# v0_6_1.net
KiCad netlist of a schematic drawn in EAGLE
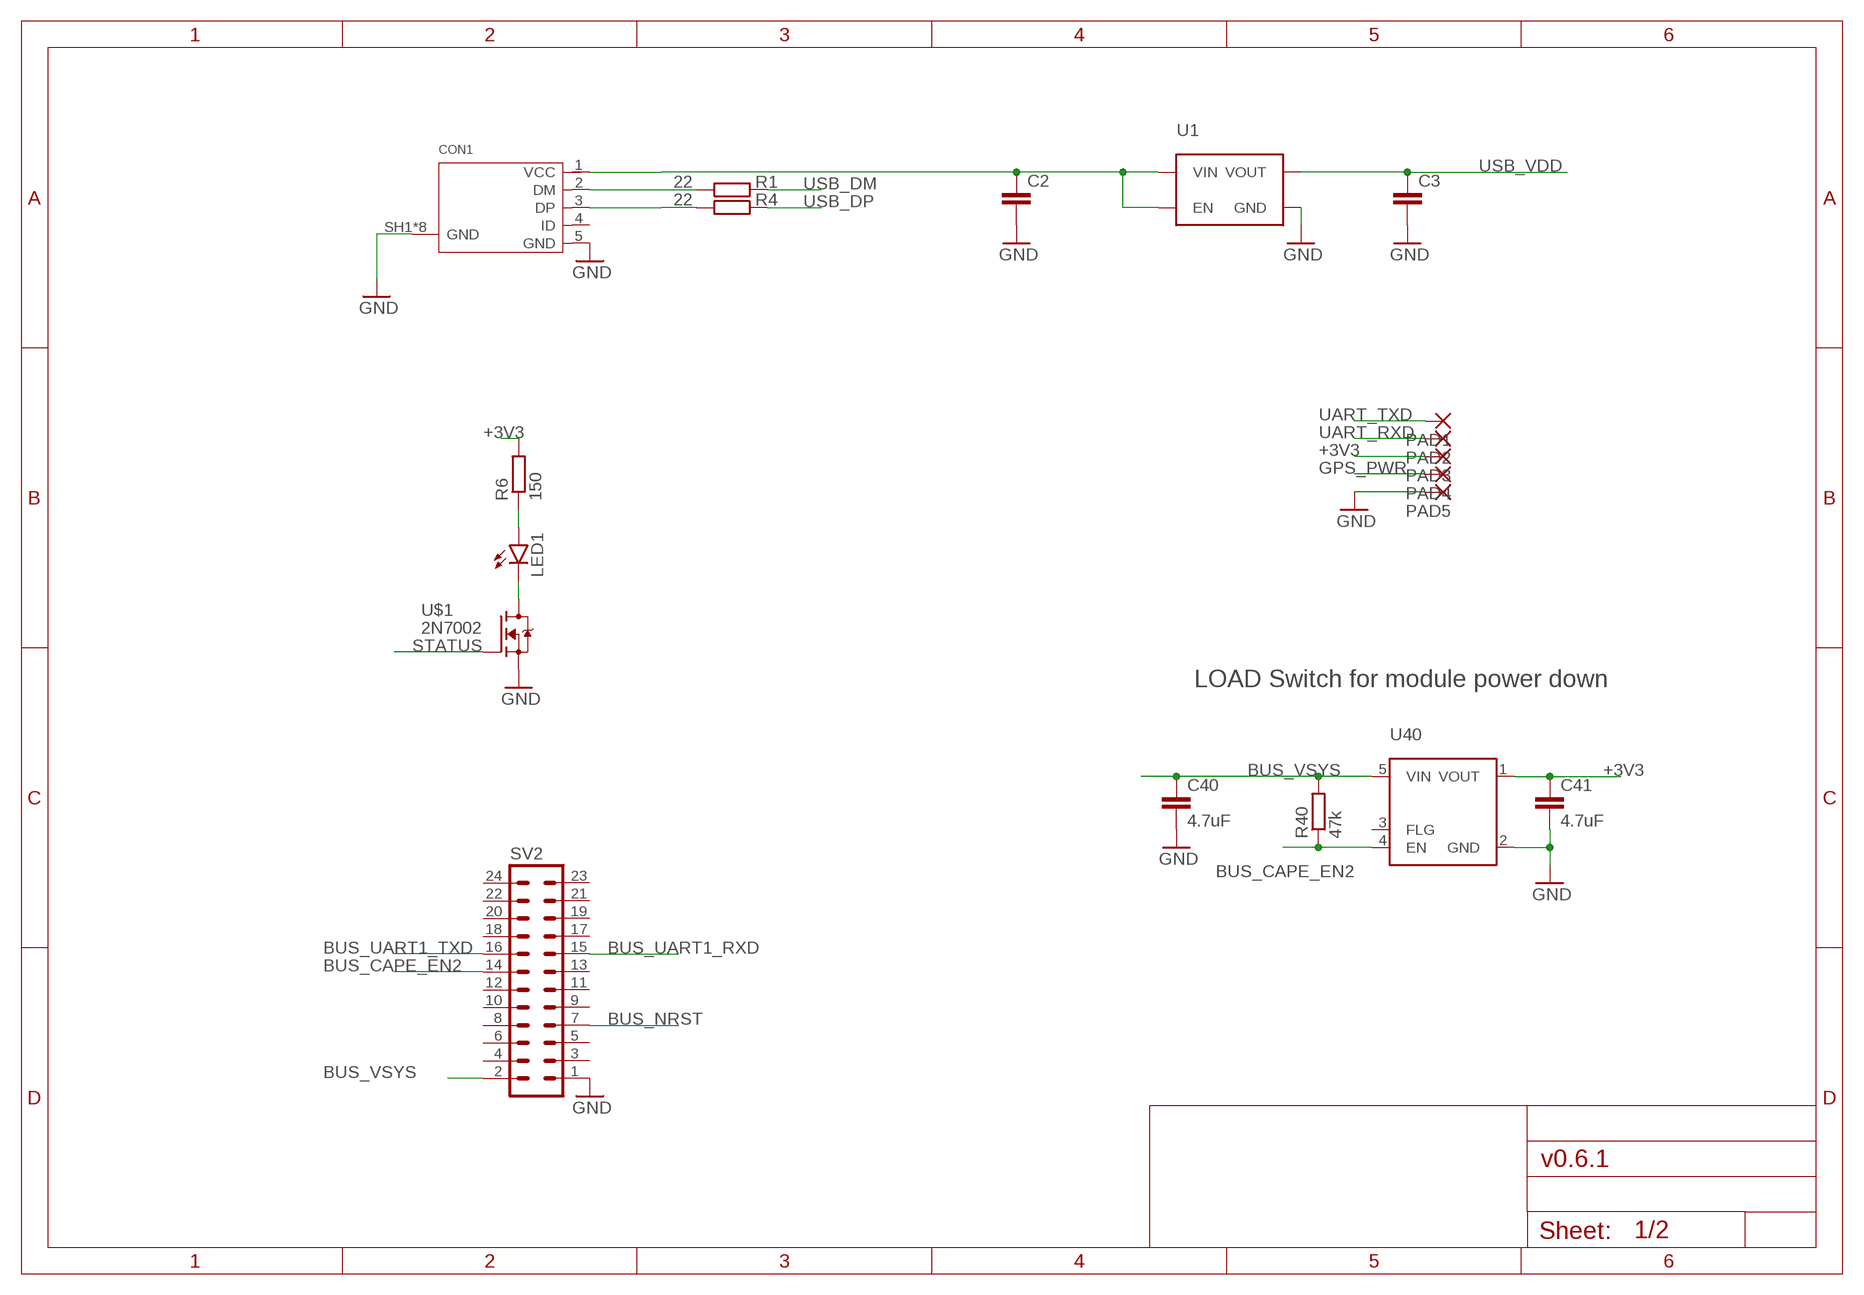
[diagram p0: schematic, sheet 1]
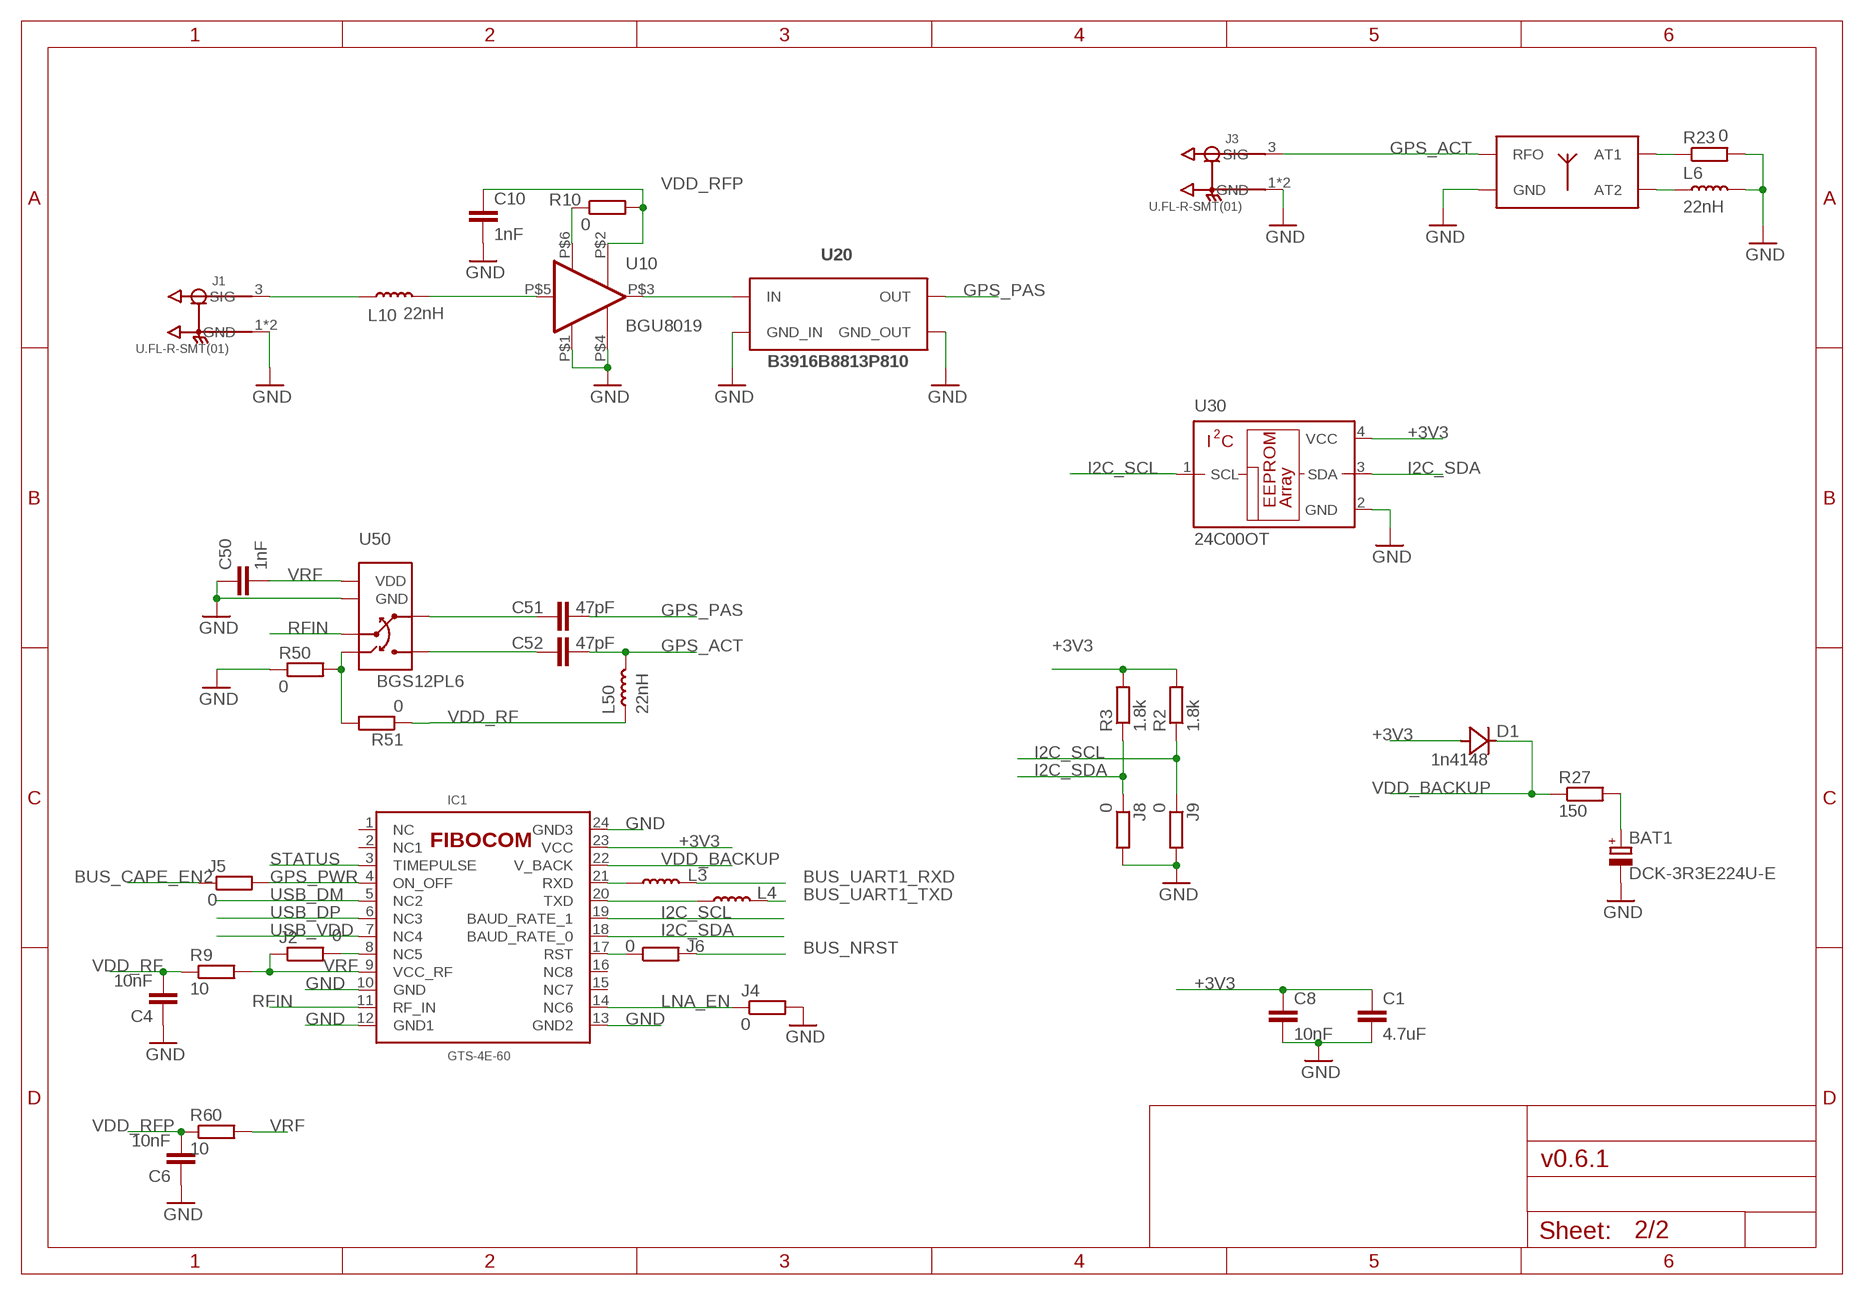
[diagram p1: schematic, sheet 2]

(export (version "E")
  (design (tool "Eeschema 10.0.6"))
  (components
    (comp (ref "ANT1")
      (value "M20047")
      (footprint "eagle-import:PCBCOMPONENT_1")
      (libsource (lib "eagle-import") (part "M20047"))
    )
    (comp (ref "BAT1")
      (value "DCK-3R3E224U-E")
      (footprint "eagle-import:621")
      (libsource (lib "eagle-import") (part "DCK-3R3E224U-E"))
    )
    (comp (ref "C1")
      (value "4.7uF")
      (footprint "eagle-import:C0603")
      (libsource (lib "eagle-import") (part "C-EUC0603"))
    )
    (comp (ref "C4")
      (value "10nF")
      (footprint "eagle-import:C0402K")
      (libsource (lib "eagle-import") (part "CAP-0402"))
    )
    (comp (ref "C6")
      (value "10nF")
      (footprint "eagle-import:C0402K")
      (libsource (lib "eagle-import") (part "CAP-0402"))
    )
    (comp (ref "C8")
      (value "10nF")
      (footprint "eagle-import:C0402K")
      (libsource (lib "eagle-import") (part "CAP-0402"))
    )
    (comp (ref "C10")
      (value "1nF")
      (footprint "eagle-import:C0402K")
      (libsource (lib "eagle-import") (part "CAP-0402"))
    )
    (comp (ref "C50")
      (value "1nF")
      (footprint "eagle-import:C0402K")
      (libsource (lib "eagle-import") (part "CAP-0402"))
    )
    (comp (ref "C51")
      (value "47pF")
      (footprint "eagle-import:C0402K")
      (libsource (lib "eagle-import") (part "CAP-0402"))
    )
    (comp (ref "C52")
      (value "47pF")
      (footprint "eagle-import:C0402K")
      (libsource (lib "eagle-import") (part "CAP-0402"))
    )
    (comp (ref "D1")
      (value "1n4148")
      (footprint "eagle-import:SOD323")
      (libsource (lib "eagle-import") (part "1N4148WS"))
    )
    (comp (ref "IC1")
      (value "GTS-4E-60")
      (footprint "eagle-import:_GTS_4E_60")
      (libsource (lib "eagle-import") (part "GTS-4E-60"))
    )
    (comp (ref "J1")
      (value "U.FL-R-SMT(01)")
      (footprint "eagle-import:HRS_U.FL-R-SMT(01)")
      (fields (field (name "MF") "Hirose") (field (name "MP") "U.FL-R-SMT_01_"))
      (libsource (lib "eagle-import") (part "U.FL-R-SMT(01)"))
    )
    (comp (ref "J2")
      (value "0")
      (footprint "eagle-import:R0402")
      (libsource (lib "eagle-import") (part "R-EU_R0402"))
    )
    (comp (ref "J3")
      (value "U.FL-R-SMT(01)")
      (footprint "eagle-import:HRS_U.FL-R-SMT(01)")
      (fields (field (name "MF") "Hirose") (field (name "MP") "U.FL-R-SMT_01_"))
      (libsource (lib "eagle-import") (part "U.FL-R-SMT(01)"))
    )
    (comp (ref "J4")
      (value "0")
      (footprint "eagle-import:R0402")
      (libsource (lib "eagle-import") (part "R-EU_R0402"))
    )
    (comp (ref "J5")
      (value "0")
      (footprint "eagle-import:R0402")
      (libsource (lib "eagle-import") (part "R-EU_R0402"))
    )
    (comp (ref "J6")
      (value "0")
      (footprint "eagle-import:R0402")
      (libsource (lib "eagle-import") (part "R-EU_R0402"))
    )
    (comp (ref "J8")
      (value "0")
      (footprint "eagle-import:R0402")
      (libsource (lib "eagle-import") (part "R-EU_R0402"))
    )
    (comp (ref "J9")
      (value "0")
      (footprint "eagle-import:R0402")
      (libsource (lib "eagle-import") (part "R-EU_R0402"))
    )
    (comp (ref "L3")
      (value "blm15")
      (footprint "eagle-import:L0402")
      (libsource (lib "eagle-import") (part "IND-0402"))
    )
    (comp (ref "L4")
      (value "blm15")
      (footprint "eagle-import:L0402")
      (libsource (lib "eagle-import") (part "IND-0402"))
    )
    (comp (ref "L6")
      (value "22nH")
      (footprint "eagle-import:L0402")
      (libsource (lib "eagle-import") (part "IND-0402"))
    )
    (comp (ref "L10")
      (value "22nH")
      (footprint "eagle-import:L0402")
      (libsource (lib "eagle-import") (part "IND-0402"))
    )
    (comp (ref "L50")
      (value "22nH")
      (footprint "eagle-import:L0402")
      (libsource (lib "eagle-import") (part "IND-0402"))
    )
    (comp (ref "R2")
      (value "1.8k")
      (footprint "eagle-import:R0402")
      (libsource (lib "eagle-import") (part "R-EU_R0402"))
    )
    (comp (ref "R3")
      (value "1.8k")
      (footprint "eagle-import:R0402")
      (libsource (lib "eagle-import") (part "R-EU_R0402"))
    )
    (comp (ref "R9")
      (value "10")
      (footprint "eagle-import:R0402")
      (libsource (lib "eagle-import") (part "R-EU_R0402"))
    )
    (comp (ref "R10")
      (value "0")
      (footprint "eagle-import:R0402")
      (libsource (lib "eagle-import") (part "R-EU_R0402"))
    )
    (comp (ref "R23")
      (value "0")
      (footprint "eagle-import:R0402")
      (libsource (lib "eagle-import") (part "R-EU_R0402"))
    )
    (comp (ref "R27")
      (value "150")
      (footprint "eagle-import:R0402")
      (libsource (lib "eagle-import") (part "R-EU_R0402"))
    )
    (comp (ref "R50")
      (value "0")
      (footprint "eagle-import:R0402")
      (libsource (lib "eagle-import") (part "R-EU_R0402"))
    )
    (comp (ref "R51")
      (value "0")
      (footprint "eagle-import:R0402")
      (libsource (lib "eagle-import") (part "R-EU_R0402"))
    )
    (comp (ref "R60")
      (value "10")
      (footprint "eagle-import:R0402")
      (libsource (lib "eagle-import") (part "R-EU_R0402"))
    )
    (comp (ref "U10")
      (value "BGU8019")
      (footprint "eagle-import:XSON6")
      (libsource (lib "eagle-import") (part "BGU8019"))
    )
    (comp (ref "U20")
      (value "B3916B8813P810")
      (footprint "eagle-import:XSON5")
      (libsource (lib "eagle-import") (part "B3916B8813P810"))
    )
    (comp (ref "U30")
      (value "24C00OT")
      (footprint "eagle-import:SOT23-5L")
      (fields (field (name "MF") "MICROCHIP") (field (name "MPN") "24C00T-I/OT"))
      (libsource (lib "eagle-import") (part "2400OTC"))
    )
    (comp (ref "U50")
      (value "BGS12PL6")
      (footprint "eagle-import:TSLP-6-4")
      (libsource (lib "eagle-import") (part "BGS12PL6"))
    )
    (comp (ref "C2")
      (value "C-EUC0603")
      (footprint "eagle-import:C0603")
      (libsource (lib "eagle-import") (part "C-EUC0603"))
    )
    (comp (ref "C3")
      (value "C-EUC0603")
      (footprint "eagle-import:C0603")
      (libsource (lib "eagle-import") (part "C-EUC0603"))
    )
    (comp (ref "C40")
      (value "4.7uF")
      (footprint "eagle-import:C0603")
      (libsource (lib "eagle-import") (part "C-EUC0603"))
    )
    (comp (ref "C41")
      (value "4.7uF")
      (footprint "eagle-import:C0603")
      (libsource (lib "eagle-import") (part "C-EUC0603"))
    )
    (comp (ref "CON1")
      (value "10118194-0001LF")
      (footprint "eagle-import:10118194")
      (libsource (lib "eagle-import") (part "10118194-0001LF"))
    )
    (comp (ref "LED1")
      (value "LEDCHIP-LED0603")
      (footprint "eagle-import:CHIP-LED0603")
      (libsource (lib "eagle-import") (part "LEDCHIP-LED0603"))
    )
    (comp (ref "PAD1")
      (value "1,6/0,9")
      (footprint "eagle-import:1,6_0,9")
      (libsource (lib "eagle-import") (part "1,6/0,9"))
    )
    (comp (ref "PAD2")
      (value "1,6/0,9")
      (footprint "eagle-import:1,6_0,9")
      (libsource (lib "eagle-import") (part "1,6/0,9"))
    )
    (comp (ref "PAD3")
      (value "1,6/0,9")
      (footprint "eagle-import:1,6_0,9")
      (libsource (lib "eagle-import") (part "1,6/0,9"))
    )
    (comp (ref "PAD4")
      (value "1,6/0,9")
      (footprint "eagle-import:1,6_0,9")
      (libsource (lib "eagle-import") (part "1,6/0,9"))
    )
    (comp (ref "PAD5")
      (value "1,6/0,9")
      (footprint "eagle-import:1,6_0,9")
      (libsource (lib "eagle-import") (part "1,6/0,9"))
    )
    (comp (ref "R1")
      (value "22")
      (footprint "eagle-import:R0402")
      (libsource (lib "eagle-import") (part "R-EU_R0402"))
    )
    (comp (ref "R4")
      (value "22")
      (footprint "eagle-import:R0402")
      (libsource (lib "eagle-import") (part "R-EU_R0402"))
    )
    (comp (ref "R6")
      (value "150")
      (footprint "eagle-import:R0402")
      (libsource (lib "eagle-import") (part "R-EU_R0402"))
    )
    (comp (ref "R40")
      (value "47k")
      (footprint "eagle-import:R0402")
      (libsource (lib "eagle-import") (part "R-EU_R0402"))
    )
    (comp (ref "SV2")
      (value "MA12-2")
      (footprint "eagle-import:MA12-2")
      (libsource (lib "eagle-import") (part "MA12-2"))
    )
    (comp (ref "U$1")
      (value "2N7002")
      (footprint "eagle-import:SOT95P240X110-3")
      (libsource (lib "eagle-import") (part "2N7002"))
    )
    (comp (ref "U1")
      (value "MIC94310")
      (footprint "eagle-import:SOT95P280X110-5")
      (libsource (lib "eagle-import") (part "MIC94310"))
    )
    (comp (ref "U40")
      (value "AP22802b")
      (footprint "eagle-import:SOT25")
      (libsource (lib "eagle-import") (part "AP22802"))
    )
  )
  (nets
    (net (code "1") (name "+3V3") (class "Default")
      (node (ref "C1") (pin "1") (pinfunction "1_1") (pintype "passive"))
      (node (ref "C41") (pin "1") (pinfunction "1_1") (pintype "passive"))
      (node (ref "C8") (pin "1") (pinfunction "1_1") (pintype "passive"))
      (node (ref "D1") (pin "A") (pinfunction "A_A") (pintype "passive"))
      (node (ref "IC1") (pin "23") (pinfunction "VCC_23") (pintype "bidirectional"))
      (node (ref "PAD3") (pin "1") (pinfunction "P_1") (pintype "passive"))
      (node (ref "R2") (pin "2") (pinfunction "2_2") (pintype "passive"))
      (node (ref "R3") (pin "2") (pinfunction "2_2") (pintype "passive"))
      (node (ref "R6") (pin "2") (pinfunction "2_2") (pintype "passive"))
      (node (ref "U30") (pin "4") (pinfunction "VCC_4") (pintype "power_in"))
      (node (ref "U40") (pin "1") (pinfunction "VOUT_1") (pintype "bidirectional"))
    )
    (net (code "2") (name "BUS_CAPE_EN2") (class "Default")
      (node (ref "J5") (pin "1") (pinfunction "1_1") (pintype "passive"))
      (node (ref "R40") (pin "1") (pinfunction "1_1") (pintype "passive"))
      (node (ref "SV2") (pin "14") (pinfunction "14_14") (pintype "passive"))
      (node (ref "U40") (pin "4") (pinfunction "EN_4") (pintype "bidirectional"))
    )
    (net (code "3") (name "BUS_NRST") (class "Default")
      (node (ref "J6") (pin "2") (pinfunction "2_2") (pintype "passive"))
      (node (ref "SV2") (pin "7") (pinfunction "7_7") (pintype "passive"))
    )
    (net (code "4") (name "BUS_UART1_RXD") (class "Default")
      (node (ref "L3") (pin "2") (pinfunction "2_2") (pintype "passive"))
      (node (ref "SV2") (pin "15") (pinfunction "15_15") (pintype "passive"))
    )
    (net (code "5") (name "BUS_UART1_TXD") (class "Default")
      (node (ref "L4") (pin "2") (pinfunction "2_2") (pintype "passive"))
      (node (ref "SV2") (pin "16") (pinfunction "16_16") (pintype "passive"))
    )
    (net (code "6") (name "BUS_VSYS") (class "Default")
      (node (ref "C40") (pin "1") (pinfunction "1_1") (pintype "passive"))
      (node (ref "R40") (pin "2") (pinfunction "2_2") (pintype "passive"))
      (node (ref "SV2") (pin "2") (pinfunction "2_2") (pintype "passive"))
      (node (ref "U40") (pin "5") (pinfunction "VIN_5") (pintype "bidirectional"))
    )
    (net (code "7") (name "GND") (class "Default")
      (node (ref "ANT1") (pin "2") (pinfunction "GND_2") (pintype "power_in"))
      (node (ref "ANT1") (pin "3") (pinfunction "GND_3") (pintype "power_in"))
      (node (ref "ANT1") (pin "4") (pinfunction "GND_4") (pintype "power_in"))
      (node (ref "BAT1") (pin "-") (pinfunction "-_-") (pintype "passive"))
      (node (ref "C1") (pin "2") (pinfunction "2_2") (pintype "passive"))
      (node (ref "C10") (pin "2") (pinfunction "2_2") (pintype "passive"))
      (node (ref "C2") (pin "2") (pinfunction "2_2") (pintype "passive"))
      (node (ref "C3") (pin "2") (pinfunction "2_2") (pintype "passive"))
      (node (ref "C4") (pin "1") (pinfunction "1_1") (pintype "passive"))
      (node (ref "C40") (pin "2") (pinfunction "2_2") (pintype "passive"))
      (node (ref "C41") (pin "2") (pinfunction "2_2") (pintype "passive"))
      (node (ref "C50") (pin "1") (pinfunction "1_1") (pintype "passive"))
      (node (ref "C6") (pin "1") (pinfunction "1_1") (pintype "passive"))
      (node (ref "C8") (pin "2") (pinfunction "2_2") (pintype "passive"))
      (node (ref "CON1") (pin "5") (pinfunction "GND_5") (pintype "bidirectional"))
      (node (ref "CON1") (pin "SH1") (pinfunction "GND_SH1") (pintype "bidirectional"))
      (node (ref "CON1") (pin "SH2") (pinfunction "GND_SH2") (pintype "bidirectional"))
      (node (ref "CON1") (pin "SH3") (pinfunction "GND_SH3") (pintype "bidirectional"))
      (node (ref "CON1") (pin "SH4") (pinfunction "GND_SH4") (pintype "bidirectional"))
      (node (ref "CON1") (pin "SH5") (pinfunction "GND_SH5") (pintype "bidirectional"))
      (node (ref "CON1") (pin "SH6") (pinfunction "GND_SH6") (pintype "bidirectional"))
      (node (ref "CON1") (pin "SH7") (pinfunction "GND_SH7") (pintype "bidirectional"))
      (node (ref "CON1") (pin "SH8") (pinfunction "GND_SH8") (pintype "bidirectional"))
      (node (ref "IC1") (pin "10") (pinfunction "GND_10") (pintype "bidirectional"))
      (node (ref "IC1") (pin "12") (pinfunction "GND1_12") (pintype "bidirectional"))
      (node (ref "IC1") (pin "13") (pinfunction "GND2_13") (pintype "bidirectional"))
      (node (ref "IC1") (pin "24") (pinfunction "GND3_24") (pintype "bidirectional"))
      (node (ref "J1") (pin "1") (pinfunction "GND_1") (pintype "passive"))
      (node (ref "J1") (pin "2") (pinfunction "GND_2") (pintype "passive"))
      (node (ref "J3") (pin "1") (pinfunction "GND_1") (pintype "passive"))
      (node (ref "J3") (pin "2") (pinfunction "GND_2") (pintype "passive"))
      (node (ref "J4") (pin "2") (pinfunction "2_2") (pintype "passive"))
      (node (ref "J8") (pin "2") (pinfunction "2_2") (pintype "passive"))
      (node (ref "J9") (pin "2") (pinfunction "2_2") (pintype "passive"))
      (node (ref "L6") (pin "2") (pinfunction "2_2") (pintype "passive"))
      (node (ref "PAD5") (pin "1") (pinfunction "P_1") (pintype "passive"))
      (node (ref "R23") (pin "2") (pinfunction "2_2") (pintype "passive"))
      (node (ref "R50") (pin "1") (pinfunction "1_1") (pintype "passive"))
      (node (ref "SV2") (pin "1") (pinfunction "1_1") (pintype "passive"))
      (node (ref "U$1") (pin "2") (pinfunction "S_2") (pintype "passive"))
      (node (ref "U1") (pin "2") (pinfunction "GND_2") (pintype "bidirectional"))
      (node (ref "U10") (pin "P$1") (pinfunction "GND_P$1") (pintype "power_in"))
      (node (ref "U10") (pin "P$4") (pinfunction "GND_RF_P$4") (pintype "passive"))
      (node (ref "U20") (pin "2") (pinfunction "GND_IN_2") (pintype "bidirectional"))
      (node (ref "U20") (pin "3") (pinfunction "GND_OUT_3") (pintype "bidirectional"))
      (node (ref "U20") (pin "5") (pinfunction "GND_IN_5") (pintype "bidirectional"))
      (node (ref "U30") (pin "2") (pinfunction "GND_2") (pintype "power_in"))
      (node (ref "U40") (pin "2") (pinfunction "GND_2") (pintype "bidirectional"))
      (node (ref "U50") (pin "P$2") (pinfunction "GND_P$2") (pintype "power_in"))
    )
    (net (code "8") (name "GPS_ACT") (class "Default")
      (node (ref "ANT1") (pin "5") (pinfunction "RFO_5") (pintype "input"))
      (node (ref "C52") (pin "2") (pinfunction "2_2") (pintype "passive"))
      (node (ref "J3") (pin "3") (pinfunction "SIG_3") (pintype "passive"))
      (node (ref "L50") (pin "2") (pinfunction "2_2") (pintype "passive"))
    )
    (net (code "9") (name "GPS_PAS") (class "Default")
      (node (ref "C51") (pin "2") (pinfunction "2_2") (pintype "passive"))
      (node (ref "U20") (pin "4") (pinfunction "OUT_4") (pintype "bidirectional"))
    )
    (net (code "10") (name "GPS_PWR") (class "Default")
      (node (ref "IC1") (pin "4") (pinfunction "ON_OFF_4") (pintype "bidirectional"))
      (node (ref "J5") (pin "2") (pinfunction "2_2") (pintype "passive"))
      (node (ref "PAD4") (pin "1") (pinfunction "P_1") (pintype "passive"))
    )
    (net (code "11") (name "I2C_SCL") (class "Default")
      (node (ref "IC1") (pin "19") (pinfunction "BAUD_RATE_1_19") (pintype "bidirectional"))
      (node (ref "J9") (pin "1") (pinfunction "1_1") (pintype "passive"))
      (node (ref "R2") (pin "1") (pinfunction "1_1") (pintype "passive"))
      (node (ref "U30") (pin "1") (pinfunction "SCL_1") (pintype "input"))
    )
    (net (code "12") (name "I2C_SDA") (class "Default")
      (node (ref "IC1") (pin "18") (pinfunction "BAUD_RATE_0_18") (pintype "bidirectional"))
      (node (ref "J8") (pin "1") (pinfunction "1_1") (pintype "passive"))
      (node (ref "R3") (pin "1") (pinfunction "1_1") (pintype "passive"))
      (node (ref "U30") (pin "3") (pinfunction "SDA_3") (pintype "bidirectional"))
    )
    (net (code "13") (name "LNA_EN") (class "Default")
      (node (ref "IC1") (pin "14") (pinfunction "NC6_14") (pintype "bidirectional"))
      (node (ref "J4") (pin "1") (pinfunction "1_1") (pintype "passive"))
    )
    (net (code "14") (name "Net-(ANT1-AT1)") (class "Default")
      (node (ref "ANT1") (pin "1") (pinfunction "AT1_1") (pintype "bidirectional"))
      (node (ref "R23") (pin "1") (pinfunction "1_1") (pintype "passive"))
    )
    (net (code "15") (name "Net-(ANT1-AT2)") (class "Default")
      (node (ref "ANT1") (pin "6") (pinfunction "AT2_6") (pintype "bidirectional"))
      (node (ref "L6") (pin "1") (pinfunction "1_1") (pintype "passive"))
    )
    (net (code "16") (name "Net-(BAT1-Pad+)") (class "Default")
      (node (ref "BAT1") (pin "+") (pinfunction "+_+") (pintype "passive"))
      (node (ref "R27") (pin "2") (pinfunction "2_2") (pintype "passive"))
    )
    (net (code "17") (name "Net-(CON1-DM)") (class "Default")
      (node (ref "CON1") (pin "2") (pinfunction "DM_2") (pintype "bidirectional"))
      (node (ref "R1") (pin "2") (pinfunction "2_2") (pintype "passive"))
    )
    (net (code "18") (name "Net-(CON1-DP)") (class "Default")
      (node (ref "CON1") (pin "3") (pinfunction "DP_3") (pintype "bidirectional"))
      (node (ref "R4") (pin "2") (pinfunction "2_2") (pintype "passive"))
    )
    (net (code "19") (name "Net-(CON1-VCC)") (class "Default")
      (node (ref "C2") (pin "1") (pinfunction "1_1") (pintype "passive"))
      (node (ref "CON1") (pin "1") (pinfunction "VCC_1") (pintype "bidirectional"))
      (node (ref "U1") (pin "1") (pinfunction "VIN_1") (pintype "bidirectional"))
      (node (ref "U1") (pin "3") (pinfunction "EN_3") (pintype "bidirectional"))
    )
    (net (code "20") (name "Net-(IC1-NC5)") (class "Default")
      (node (ref "IC1") (pin "8") (pinfunction "NC5_8") (pintype "bidirectional"))
      (node (ref "J2") (pin "2") (pinfunction "2_2") (pintype "passive"))
    )
    (net (code "21") (name "Net-(IC1-RST)") (class "Default")
      (node (ref "IC1") (pin "17") (pinfunction "RST_17") (pintype "bidirectional"))
      (node (ref "J6") (pin "1") (pinfunction "1_1") (pintype "passive"))
    )
    (net (code "22") (name "Net-(J1-SIG)") (class "Default")
      (node (ref "J1") (pin "3") (pinfunction "SIG_3") (pintype "passive"))
      (node (ref "L10") (pin "1") (pinfunction "1_1") (pintype "passive"))
    )
    (net (code "23") (name "Net-(LED1-PadA)") (class "Default")
      (node (ref "LED1") (pin "A") (pinfunction "A_A") (pintype "passive"))
      (node (ref "R6") (pin "1") (pinfunction "1_1") (pintype "passive"))
    )
    (net (code "24") (name "Net-(U$1-D)") (class "Default")
      (node (ref "LED1") (pin "C") (pinfunction "C_C") (pintype "passive"))
      (node (ref "U$1") (pin "3") (pinfunction "D_3") (pintype "passive"))
    )
    (net (code "25") (name "Net-(U10-ENABLE)") (class "Default")
      (node (ref "R10") (pin "1") (pinfunction "1_1") (pintype "passive"))
      (node (ref "U10") (pin "P$6") (pinfunction "ENABLE_P$6") (pintype "power_in"))
    )
    (net (code "26") (name "Net-(U10-RF_IN)") (class "Default")
      (node (ref "L10") (pin "2") (pinfunction "2_2") (pintype "passive"))
      (node (ref "U10") (pin "P$5") (pinfunction "RF_IN_P$5") (pintype "input"))
    )
    (net (code "27") (name "Net-(U10-RF_OUT)") (class "Default")
      (node (ref "U10") (pin "P$3") (pinfunction "RF_OUT_P$3") (pintype "output"))
      (node (ref "U20") (pin "1") (pinfunction "IN_1") (pintype "bidirectional"))
    )
    (net (code "28") (name "Net-(U50-P$4)") (class "Default")
      (node (ref "R50") (pin "2") (pinfunction "2_2") (pintype "passive"))
      (node (ref "R51") (pin "2") (pinfunction "2_2") (pintype "passive"))
      (node (ref "U50") (pin "P$6") (pinfunction "P$4_P$6") (pintype "bidirectional"))
    )
    (net (code "29") (name "Net-(U50-RF1)") (class "Default")
      (node (ref "C51") (pin "1") (pinfunction "1_1") (pintype "passive"))
      (node (ref "U50") (pin "P$3") (pinfunction "RF1_P$3") (pintype "bidirectional"))
    )
    (net (code "30") (name "Net-(U50-RF2)") (class "Default")
      (node (ref "C52") (pin "1") (pinfunction "1_1") (pintype "passive"))
      (node (ref "U50") (pin "P$1") (pinfunction "RF2_P$1") (pintype "bidirectional"))
    )
    (net (code "31") (name "RFIN") (class "Default")
      (node (ref "IC1") (pin "11") (pinfunction "RF_IN_11") (pintype "bidirectional"))
      (node (ref "U50") (pin "P$5") (pinfunction "RFIN_P$5") (pintype "bidirectional"))
    )
    (net (code "32") (name "STATUS") (class "Default")
      (node (ref "IC1") (pin "3") (pinfunction "TIMEPULSE_3") (pintype "bidirectional"))
      (node (ref "U$1") (pin "1") (pinfunction "G_1") (pintype "passive"))
    )
    (net (code "33") (name "UART_RXD") (class "Default")
      (node (ref "IC1") (pin "20") (pinfunction "TXD_20") (pintype "bidirectional"))
      (node (ref "L4") (pin "1") (pinfunction "1_1") (pintype "passive"))
      (node (ref "PAD2") (pin "1") (pinfunction "P_1") (pintype "passive"))
    )
    (net (code "34") (name "UART_TXD") (class "Default")
      (node (ref "IC1") (pin "21") (pinfunction "RXD_21") (pintype "bidirectional"))
      (node (ref "L3") (pin "1") (pinfunction "1_1") (pintype "passive"))
      (node (ref "PAD1") (pin "1") (pinfunction "P_1") (pintype "passive"))
    )
    (net (code "35") (name "USB_DM") (class "Default")
      (node (ref "IC1") (pin "5") (pinfunction "NC2_5") (pintype "bidirectional"))
      (node (ref "R1") (pin "1") (pinfunction "1_1") (pintype "passive"))
    )
    (net (code "36") (name "USB_DP") (class "Default")
      (node (ref "IC1") (pin "6") (pinfunction "NC3_6") (pintype "bidirectional"))
      (node (ref "R4") (pin "1") (pinfunction "1_1") (pintype "passive"))
    )
    (net (code "37") (name "USB_VDD") (class "Default")
      (node (ref "C3") (pin "1") (pinfunction "1_1") (pintype "passive"))
      (node (ref "IC1") (pin "7") (pinfunction "NC4_7") (pintype "bidirectional"))
      (node (ref "U1") (pin "5") (pinfunction "VOUT_5") (pintype "bidirectional"))
    )
    (net (code "38") (name "VDD_BACKUP") (class "Default")
      (node (ref "D1") (pin "K") (pinfunction "C_K") (pintype "passive"))
      (node (ref "IC1") (pin "22") (pinfunction "V_BACK_22") (pintype "bidirectional"))
      (node (ref "R27") (pin "1") (pinfunction "1_1") (pintype "passive"))
    )
    (net (code "39") (name "VDD_RF") (class "Default")
      (node (ref "C4") (pin "2") (pinfunction "2_2") (pintype "passive"))
      (node (ref "L50") (pin "1") (pinfunction "1_1") (pintype "passive"))
      (node (ref "R51") (pin "1") (pinfunction "1_1") (pintype "passive"))
      (node (ref "R9") (pin "1") (pinfunction "1_1") (pintype "passive"))
    )
    (net (code "40") (name "VDD_RFP") (class "Default")
      (node (ref "C10") (pin "1") (pinfunction "1_1") (pintype "passive"))
      (node (ref "C6") (pin "2") (pinfunction "2_2") (pintype "passive"))
      (node (ref "R10") (pin "2") (pinfunction "2_2") (pintype "passive"))
      (node (ref "R60") (pin "1") (pinfunction "1_1") (pintype "passive"))
      (node (ref "U10") (pin "P$2") (pinfunction "VCC_P$2") (pintype "passive"))
    )
    (net (code "41") (name "VRF") (class "Default")
      (node (ref "C50") (pin "2") (pinfunction "2_2") (pintype "passive"))
      (node (ref "IC1") (pin "9") (pinfunction "VCC_RF_9") (pintype "bidirectional"))
      (node (ref "J2") (pin "1") (pinfunction "1_1") (pintype "passive"))
      (node (ref "R60") (pin "2") (pinfunction "2_2") (pintype "passive"))
      (node (ref "R9") (pin "2") (pinfunction "2_2") (pintype "passive"))
      (node (ref "U50") (pin "P$4") (pinfunction "VDD_P$4") (pintype "power_in"))
    )
    (net (code "42") (name "unconnected-(CON1-ID-Pad4)") (class "Default")
      (node (ref "CON1") (pin "4") (pinfunction "ID_4") (pintype "bidirectional"))
    )
    (net (code "43") (name "unconnected-(IC1-NC-Pad1)") (class "Default")
      (node (ref "IC1") (pin "1") (pinfunction "NC_1") (pintype "bidirectional"))
    )
    (net (code "44") (name "unconnected-(IC1-NC1-Pad2)") (class "Default")
      (node (ref "IC1") (pin "2") (pinfunction "NC1_2") (pintype "bidirectional"))
    )
    (net (code "45") (name "unconnected-(IC1-NC7-Pad15)") (class "Default")
      (node (ref "IC1") (pin "15") (pinfunction "NC7_15") (pintype "bidirectional"))
    )
    (net (code "46") (name "unconnected-(IC1-NC8-Pad16)") (class "Default")
      (node (ref "IC1") (pin "16") (pinfunction "NC8_16") (pintype "bidirectional"))
    )
    (net (code "47") (name "unconnected-(SV2-Pad3)") (class "Default")
      (node (ref "SV2") (pin "3") (pinfunction "3_3") (pintype "passive"))
    )
    (net (code "48") (name "unconnected-(SV2-Pad4)") (class "Default")
      (node (ref "SV2") (pin "4") (pinfunction "4_4") (pintype "passive"))
    )
    (net (code "49") (name "unconnected-(SV2-Pad5)") (class "Default")
      (node (ref "SV2") (pin "5") (pinfunction "5_5") (pintype "passive"))
    )
    (net (code "50") (name "unconnected-(SV2-Pad6)") (class "Default")
      (node (ref "SV2") (pin "6") (pinfunction "6_6") (pintype "passive"))
    )
    (net (code "51") (name "unconnected-(SV2-Pad8)") (class "Default")
      (node (ref "SV2") (pin "8") (pinfunction "8_8") (pintype "passive"))
    )
    (net (code "52") (name "unconnected-(SV2-Pad9)") (class "Default")
      (node (ref "SV2") (pin "9") (pinfunction "9_9") (pintype "passive"))
    )
    (net (code "53") (name "unconnected-(SV2-Pad10)") (class "Default")
      (node (ref "SV2") (pin "10") (pinfunction "10_10") (pintype "passive"))
    )
    (net (code "54") (name "unconnected-(SV2-Pad11)") (class "Default")
      (node (ref "SV2") (pin "11") (pinfunction "11_11") (pintype "passive"))
    )
    (net (code "55") (name "unconnected-(SV2-Pad12)") (class "Default")
      (node (ref "SV2") (pin "12") (pinfunction "12_12") (pintype "passive"))
    )
    (net (code "56") (name "unconnected-(SV2-Pad13)") (class "Default")
      (node (ref "SV2") (pin "13") (pinfunction "13_13") (pintype "passive"))
    )
    (net (code "57") (name "unconnected-(SV2-Pad17)") (class "Default")
      (node (ref "SV2") (pin "17") (pinfunction "17_17") (pintype "passive"))
    )
    (net (code "58") (name "unconnected-(SV2-Pad18)") (class "Default")
      (node (ref "SV2") (pin "18") (pinfunction "18_18") (pintype "passive"))
    )
    (net (code "59") (name "unconnected-(SV2-Pad19)") (class "Default")
      (node (ref "SV2") (pin "19") (pinfunction "19_19") (pintype "passive"))
    )
    (net (code "60") (name "unconnected-(SV2-Pad20)") (class "Default")
      (node (ref "SV2") (pin "20") (pinfunction "20_20") (pintype "passive"))
    )
    (net (code "61") (name "unconnected-(SV2-Pad21)") (class "Default")
      (node (ref "SV2") (pin "21") (pinfunction "21_21") (pintype "passive"))
    )
    (net (code "62") (name "unconnected-(SV2-Pad22)") (class "Default")
      (node (ref "SV2") (pin "22") (pinfunction "22_22") (pintype "passive"))
    )
    (net (code "63") (name "unconnected-(SV2-Pad23)") (class "Default")
      (node (ref "SV2") (pin "23") (pinfunction "23_23") (pintype "passive"))
    )
    (net (code "64") (name "unconnected-(SV2-Pad24)") (class "Default")
      (node (ref "SV2") (pin "24") (pinfunction "24_24") (pintype "passive"))
    )
    (net (code "65") (name "unconnected-(U40-FLG-Pad3)") (class "Default")
      (node (ref "U40") (pin "3") (pinfunction "FLG_3") (pintype "bidirectional"))
    )
  )
)
